# Interfaces.net
KiCad netlist of a schematic drawn in Altium Designer
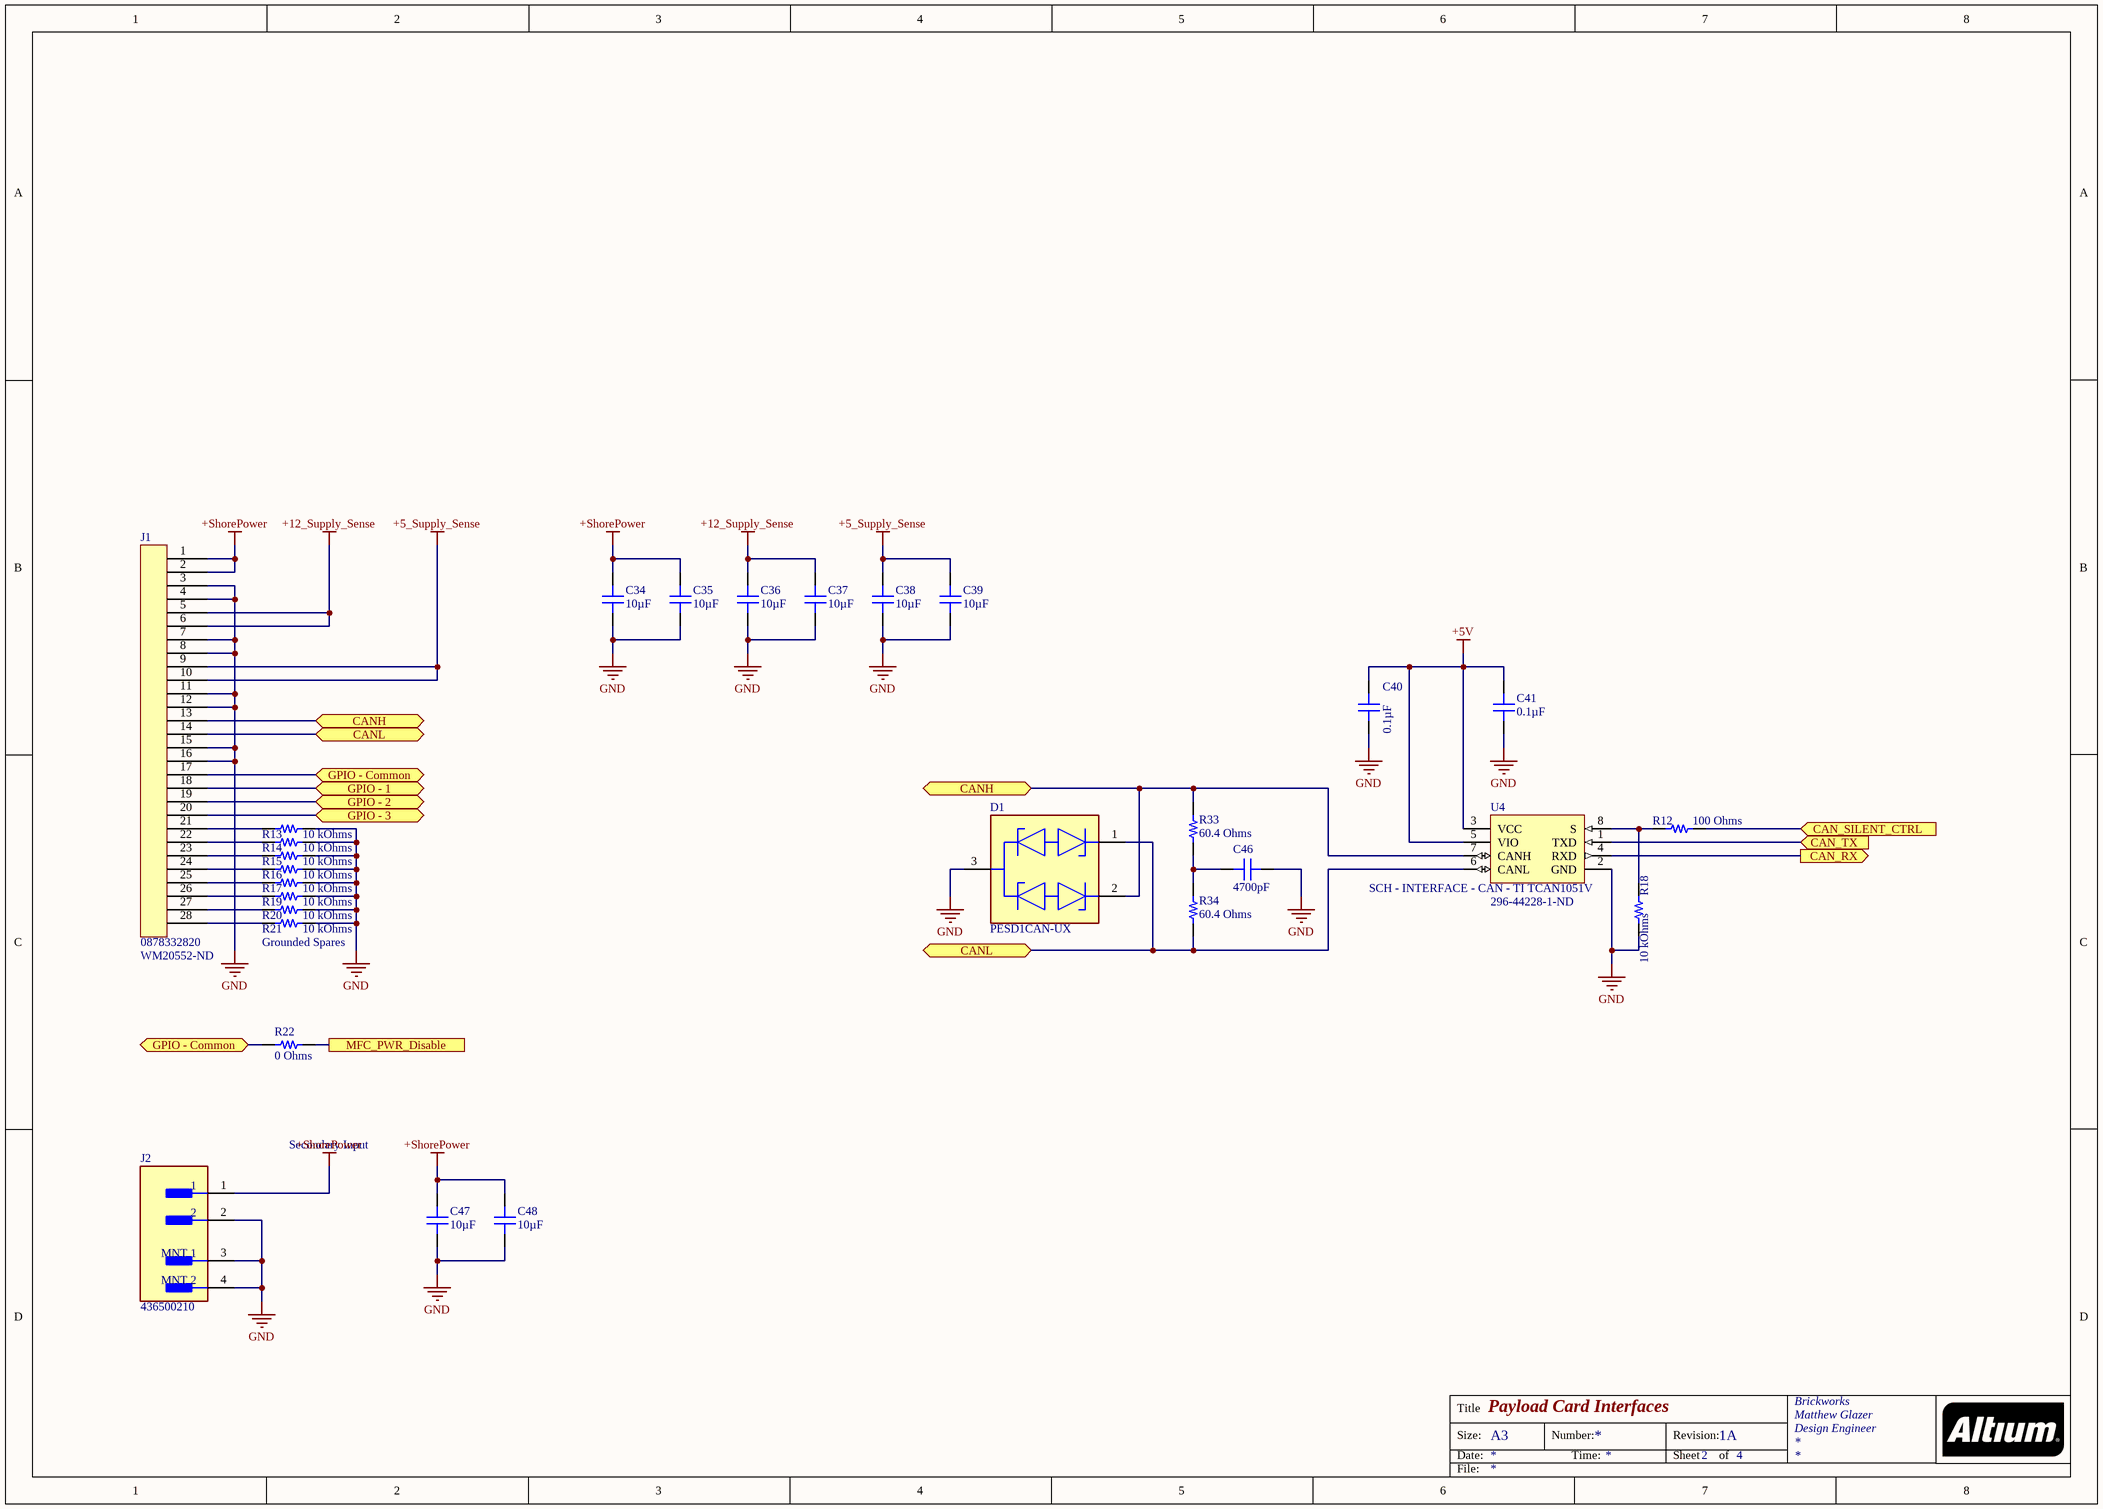
[diagram p0: Interfaces.SchDoc]

(export (version "E")
  (design (tool "Eeschema 10.0.6"))
  (components
    (comp (ref "C34")
      (value "10µF")
      (footprint "CAP 0805_2012")
      (description "CAP CER 10UF 16V X5R 0805")
      (fields (field (name "PART NUMBER") "CC0805KKX5R7BB106") (field (name "MANUFACTURER") "Yageo"))
      (libsource (lib "Celestial Altium Library - altium_library") (part "Capacitor"))
    )
    (comp (ref "C35")
      (value "10µF")
      (footprint "CAP 0805_2012")
      (description "CAP CER 10UF 16V X5R 0805")
      (fields (field (name "PART NUMBER") "CC0805KKX5R7BB106") (field (name "MANUFACTURER") "Yageo"))
      (libsource (lib "Celestial Altium Library - altium_library") (part "Capacitor"))
    )
    (comp (ref "C36")
      (value "10µF")
      (footprint "CAP 0805_2012")
      (description "CAP CER 10UF 16V X5R 0805")
      (fields (field (name "PART NUMBER") "CC0805KKX5R7BB106") (field (name "MANUFACTURER") "Yageo"))
      (libsource (lib "Celestial Altium Library - altium_library") (part "Capacitor"))
    )
    (comp (ref "C37")
      (value "10µF")
      (footprint "CAP 0805_2012")
      (description "CAP CER 10UF 16V X5R 0805")
      (fields (field (name "PART NUMBER") "CC0805KKX5R7BB106") (field (name "MANUFACTURER") "Yageo"))
      (libsource (lib "Celestial Altium Library - altium_library") (part "Capacitor"))
    )
    (comp (ref "C38")
      (value "10µF")
      (footprint "CAP 0805_2012")
      (description "CAP CER 10UF 16V X5R 0805")
      (fields (field (name "PART NUMBER") "CC0805KKX5R7BB106") (field (name "MANUFACTURER") "Yageo"))
      (libsource (lib "Celestial Altium Library - altium_library") (part "Capacitor"))
    )
    (comp (ref "C39")
      (value "10µF")
      (footprint "CAP 0805_2012")
      (description "CAP CER 10UF 16V X5R 0805")
      (fields (field (name "PART NUMBER") "CC0805KKX5R7BB106") (field (name "MANUFACTURER") "Yageo"))
      (libsource (lib "Celestial Altium Library - altium_library") (part "Capacitor"))
    )
    (comp (ref "C40")
      (value "0.1µF")
      (footprint "CAP 0603_1608")
      (description "CAP CER 0.1UF 25V X7R 0603")
      (fields
        (field (name "PART NUMBER") "CL10B104KA8WPNC")
        (field (name "MANUFACTURER") "Samsung Electro-Mechanics")
      )
      (libsource (lib "Celestial Altium Library - altium_library") (part "Capacitor"))
    )
    (comp (ref "C41")
      (value "0.1µF")
      (footprint "CAP 0603_1608")
      (description "CAP CER 0.1UF 25V X7R 0603")
      (fields
        (field (name "PART NUMBER") "CL10B104KA8WPNC")
        (field (name "MANUFACTURER") "Samsung Electro-Mechanics")
      )
      (libsource (lib "Celestial Altium Library - altium_library") (part "Capacitor"))
    )
    (comp (ref "C46")
      (value "4700pF")
      (footprint "CAP 0603_1608")
      (description "CAP CER 4700PF 50V X7R 0603")
      (fields
        (field (name "PART NUMBER") "VJ0603Y472KXACW1BC")
        (field (name "MANUFACTURER") "Vishay Vitramon")
      )
      (libsource (lib "Celestial Altium Library - altium_library") (part "Capacitor"))
    )
    (comp (ref "C47")
      (value "10µF")
      (footprint "CAP 0805_2012")
      (description "CAP CER 10UF 16V X5R 0805")
      (fields (field (name "PART NUMBER") "CC0805KKX5R7BB106") (field (name "MANUFACTURER") "Yageo"))
      (libsource (lib "Celestial Altium Library - altium_library") (part "Capacitor"))
    )
    (comp (ref "C48")
      (value "10µF")
      (footprint "CAP 0805_2012")
      (description "CAP CER 10UF 16V X5R 0805")
      (fields (field (name "PART NUMBER") "CC0805KKX5R7BB106") (field (name "MANUFACTURER") "Yageo"))
      (libsource (lib "Celestial Altium Library - altium_library") (part "Capacitor"))
    )
    (comp (ref "D1")
      (value "PESD1CAN-UX")
      (footprint "FP-SOT323-MFG")
      (description "TVS DIODE 24V 50V SC70-3")
      (libsource (lib "Altium Content Vault") (part "04d57993b6b7b0f5b3c95ba4f97dea0"))
    )
    (comp (ref "J1")
      (value "0878332820")
      (footprint "0878332820")
      (fields (field (name "SUPPLIER PART NUMBER 1") "WM20552-ND"))
      (libsource (lib "HAB_Connectors") (part "0878332820"))
    )
    (comp (ref "J2")
      (value "436500210")
      (footprint "FP-436500210-MFG")
      (description "CONN HEADER SMD R/A 2POS 3MM")
      (fields
        (field (name "MANUFACTURER") "Molex")
        (field (name "OCTOPART") "https://octopart.com/43650-0210-molex-298097")
      )
      (libsource (lib "Altium Content Vault") (part "029478cb6d4f2fad0cd2a245525ee6d"))
    )
    (comp (ref "R12")
      (value "100 Ohms")
      (footprint "RES 0603_1608")
      (description "RES 100 OHM 1% 1/10W 0603")
      (fields
        (field (name "PART NUMBER") "RMCF0603FG100R")
        (field (name "MANUFACTURER") "Stackpole Electronics Inc")
      )
      (libsource (lib "Celestial Altium Library - altium_library") (part "Resistor"))
    )
    (comp (ref "R13")
      (value "10 kOhms")
      (footprint "RES 0603_1608")
      (description "RES 10K OHM 5% 1/10W 0603")
      (fields
        (field (name "PART NUMBER") "RMCF0603JT10K0")
        (field (name "MANUFACTURER") "Stackpole Electronics Inc")
      )
      (libsource (lib "Celestial Altium Library - altium_library") (part "Resistor"))
    )
    (comp (ref "R14")
      (value "10 kOhms")
      (footprint "RES 0603_1608")
      (description "RES 10K OHM 5% 1/10W 0603")
      (fields
        (field (name "PART NUMBER") "RMCF0603JT10K0")
        (field (name "MANUFACTURER") "Stackpole Electronics Inc")
      )
      (libsource (lib "Celestial Altium Library - altium_library") (part "Resistor"))
    )
    (comp (ref "R15")
      (value "10 kOhms")
      (footprint "RES 0603_1608")
      (description "RES 10K OHM 5% 1/10W 0603")
      (fields
        (field (name "PART NUMBER") "RMCF0603JT10K0")
        (field (name "MANUFACTURER") "Stackpole Electronics Inc")
      )
      (libsource (lib "Celestial Altium Library - altium_library") (part "Resistor"))
    )
    (comp (ref "R16")
      (value "10 kOhms")
      (footprint "RES 0603_1608")
      (description "RES 10K OHM 5% 1/10W 0603")
      (fields
        (field (name "PART NUMBER") "RMCF0603JT10K0")
        (field (name "MANUFACTURER") "Stackpole Electronics Inc")
      )
      (libsource (lib "Celestial Altium Library - altium_library") (part "Resistor"))
    )
    (comp (ref "R17")
      (value "10 kOhms")
      (footprint "RES 0603_1608")
      (description "RES 10K OHM 5% 1/10W 0603")
      (fields
        (field (name "PART NUMBER") "RMCF0603JT10K0")
        (field (name "MANUFACTURER") "Stackpole Electronics Inc")
      )
      (libsource (lib "Celestial Altium Library - altium_library") (part "Resistor"))
    )
    (comp (ref "R18")
      (value "10 kOhms")
      (footprint "RES 0603_1608")
      (description "RES 10K OHM 5% 1/10W 0603")
      (fields
        (field (name "PART NUMBER") "RMCF0603JT10K0")
        (field (name "MANUFACTURER") "Stackpole Electronics Inc")
      )
      (libsource (lib "Celestial Altium Library - altium_library") (part "Resistor"))
    )
    (comp (ref "R19")
      (value "10 kOhms")
      (footprint "RES 0603_1608")
      (description "RES 10K OHM 5% 1/10W 0603")
      (fields
        (field (name "PART NUMBER") "RMCF0603JT10K0")
        (field (name "MANUFACTURER") "Stackpole Electronics Inc")
      )
      (libsource (lib "Celestial Altium Library - altium_library") (part "Resistor"))
    )
    (comp (ref "R20")
      (value "10 kOhms")
      (footprint "RES 0603_1608")
      (description "RES 10K OHM 5% 1/10W 0603")
      (fields
        (field (name "PART NUMBER") "RMCF0603JT10K0")
        (field (name "MANUFACTURER") "Stackpole Electronics Inc")
      )
      (libsource (lib "Celestial Altium Library - altium_library") (part "Resistor"))
    )
    (comp (ref "R21")
      (value "10 kOhms")
      (footprint "RES 0603_1608")
      (description "RES 10K OHM 5% 1/10W 0603")
      (fields
        (field (name "PART NUMBER") "RMCF0603JT10K0")
        (field (name "MANUFACTURER") "Stackpole Electronics Inc")
      )
      (libsource (lib "Celestial Altium Library - altium_library") (part "Resistor"))
    )
    (comp (ref "R22")
      (value "0 Ohms")
      (footprint "RES 0603_1608")
      (description "RES 0 OHM JUMPER 1/10W 0603")
      (fields
        (field (name "PART NUMBER") "RMCF0603ZT0R00")
        (field (name "MANUFACTURER") "Stackpole Electronics Inc")
      )
      (libsource (lib "Celestial Altium Library - altium_library") (part "Resistor"))
    )
    (comp (ref "R33")
      (value "60.4 Ohms")
      (footprint "RES 1206_3216")
      (description "RES SMD 60.4 OHM 1% 1/2W 1206")
      (fields (field (name "PART NUMBER") "ESR18EZPF60R4") (field (name "MANUFACTURER") "Rohm Semiconductor"))
      (libsource (lib "Celestial Altium Library - altium_library") (part "Resistor"))
    )
    (comp (ref "R34")
      (value "60.4 Ohms")
      (footprint "RES 1206_3216")
      (description "RES SMD 60.4 OHM 1% 1/2W 1206")
      (fields (field (name "PART NUMBER") "ESR18EZPF60R4") (field (name "MANUFACTURER") "Rohm Semiconductor"))
      (libsource (lib "Celestial Altium Library - altium_library") (part "Resistor"))
    )
    (comp (ref "U4")
      (value "SCH - INTERFACE - CAN - TI TCAN1051V")
      (footprint "PCB - LEADS - SOIC - TI SOIC-8")
      (fields (field (name "SUPPLIER PART NUMBER 1") "296-44228-1-ND"))
      (libsource (lib "HAB_ICs") (part "SCH - INTERFACE - CAN - TI TCAN1051V"))
    )
  )
  (nets
    (net (code "1") (name "+5V") (class "Default")
      (node (ref "C40") (pin "2") (pinfunction "2_2") (pintype "passive"))
      (node (ref "C41") (pin "2") (pinfunction "2_2") (pintype "passive"))
      (node (ref "U4") (pin "3") (pinfunction "VCC_3") (pintype "power_in"))
      (node (ref "U4") (pin "5") (pinfunction "VIO_5") (pintype "power_in"))
    )
    (net (code "2") (name "+5_Supply_Sense") (class "Default")
      (node (ref "C38") (pin "2") (pinfunction "2_2") (pintype "passive"))
      (node (ref "C39") (pin "2") (pinfunction "2_2") (pintype "passive"))
      (node (ref "J1") (pin "10") (pintype "passive"))
      (node (ref "J1") (pin "9") (pintype "passive"))
    )
    (net (code "3") (name "+12_Supply_Sense") (class "Default")
      (node (ref "C36") (pin "2") (pinfunction "2_2") (pintype "passive"))
      (node (ref "C37") (pin "2") (pinfunction "2_2") (pintype "passive"))
      (node (ref "J1") (pin "5") (pintype "passive"))
      (node (ref "J1") (pin "6") (pintype "passive"))
    )
    (net (code "4") (name "+ShorePower") (class "Default")
      (node (ref "C34") (pin "2") (pinfunction "2_2") (pintype "passive"))
      (node (ref "C35") (pin "2") (pinfunction "2_2") (pintype "passive"))
      (node (ref "C47") (pin "2") (pinfunction "2_2") (pintype "passive"))
      (node (ref "C48") (pin "2") (pinfunction "2_2") (pintype "passive"))
      (node (ref "J1") (pin "1") (pintype "passive"))
      (node (ref "J1") (pin "2") (pintype "passive"))
      (node (ref "J2") (pin "1") (pinfunction "1_1") (pintype "passive"))
    )
    (net (code "5") (name "/CANH") (class "Default")
      (node (ref "D1") (pin "2") (pinfunction "cathode_2_2") (pintype "passive"))
      (node (ref "J1") (pin "13") (pintype "passive"))
      (node (ref "R33") (pin "2") (pinfunction "2_2") (pintype "passive"))
      (node (ref "U4") (pin "7") (pinfunction "CANH_7") (pintype "bidirectional"))
    )
    (net (code "6") (name "/CANL") (class "Default")
      (node (ref "D1") (pin "1") (pinfunction "cathode_1_1") (pintype "passive"))
      (node (ref "J1") (pin "14") (pintype "passive"))
      (node (ref "R34") (pin "1") (pinfunction "1_1") (pintype "passive"))
      (node (ref "U4") (pin "6") (pinfunction "CANL_6") (pintype "bidirectional"))
    )
    (net (code "7") (name "/CAN_RX") (class "Default")
      (node (ref "U4") (pin "4") (pinfunction "RXD_4") (pintype "output"))
    )
    (net (code "8") (name "/CAN_SILENT_CTRL") (class "Default")
      (node (ref "R12") (pin "2") (pinfunction "2_2") (pintype "passive"))
    )
    (net (code "9") (name "/CAN_TX") (class "Default")
      (node (ref "U4") (pin "1") (pinfunction "TXD_1") (pintype "input"))
    )
    (net (code "10") (name "/GPIO - 1") (class "Default") (node (ref "J1") (pin "18") (pintype "passive")))
    (net (code "11") (name "/GPIO - 2") (class "Default") (node (ref "J1") (pin "19") (pintype "passive")))
    (net (code "12") (name "/GPIO - 3") (class "Default") (node (ref "J1") (pin "20") (pintype "passive")))
    (net (code "13") (name "/GPIO - Common") (class "Default")
      (node (ref "J1") (pin "17") (pintype "passive"))
      (node (ref "R22") (pin "1") (pinfunction "1_1") (pintype "passive"))
    )
    (net (code "14") (name "/MFC_PWR_Disable") (class "Default")
      (node (ref "R22") (pin "2") (pinfunction "2_2") (pintype "passive"))
    )
    (net (code "15") (name "GND") (class "Default")
      (node (ref "C34") (pin "1") (pinfunction "1_1") (pintype "passive"))
      (node (ref "C35") (pin "1") (pinfunction "1_1") (pintype "passive"))
      (node (ref "C36") (pin "1") (pinfunction "1_1") (pintype "passive"))
      (node (ref "C37") (pin "1") (pinfunction "1_1") (pintype "passive"))
      (node (ref "C38") (pin "1") (pinfunction "1_1") (pintype "passive"))
      (node (ref "C39") (pin "1") (pinfunction "1_1") (pintype "passive"))
      (node (ref "C40") (pin "1") (pinfunction "1_1") (pintype "passive"))
      (node (ref "C41") (pin "1") (pinfunction "1_1") (pintype "passive"))
      (node (ref "C46") (pin "2") (pinfunction "2_2") (pintype "passive"))
      (node (ref "C47") (pin "1") (pinfunction "1_1") (pintype "passive"))
      (node (ref "C48") (pin "1") (pinfunction "1_1") (pintype "passive"))
      (node (ref "D1") (pin "3") (pinfunction "common_cathode_3") (pintype "passive"))
      (node (ref "J1") (pin "11") (pintype "passive"))
      (node (ref "J1") (pin "12") (pintype "passive"))
      (node (ref "J1") (pin "15") (pintype "passive"))
      (node (ref "J1") (pin "16") (pintype "passive"))
      (node (ref "J1") (pin "3") (pintype "passive"))
      (node (ref "J1") (pin "4") (pintype "passive"))
      (node (ref "J1") (pin "7") (pintype "passive"))
      (node (ref "J1") (pin "8") (pintype "passive"))
      (node (ref "J2") (pin "2") (pinfunction "2_2") (pintype "passive"))
      (node (ref "J2") (pin "3") (pinfunction "MNT_1_3") (pintype "passive"))
      (node (ref "J2") (pin "4") (pinfunction "MNT_2_4") (pintype "passive"))
      (node (ref "R13") (pin "2") (pinfunction "2_2") (pintype "passive"))
      (node (ref "R14") (pin "2") (pinfunction "2_2") (pintype "passive"))
      (node (ref "R15") (pin "2") (pinfunction "2_2") (pintype "passive"))
      (node (ref "R16") (pin "2") (pinfunction "2_2") (pintype "passive"))
      (node (ref "R17") (pin "2") (pinfunction "2_2") (pintype "passive"))
      (node (ref "R18") (pin "1") (pinfunction "1_1") (pintype "passive"))
      (node (ref "R19") (pin "2") (pinfunction "2_2") (pintype "passive"))
      (node (ref "R20") (pin "2") (pinfunction "2_2") (pintype "passive"))
      (node (ref "R21") (pin "2") (pinfunction "2_2") (pintype "passive"))
      (node (ref "U4") (pin "2") (pinfunction "GND_2") (pintype "power_in"))
    )
    (net (code "16") (name "Net-(C46-Pad1)") (class "Default")
      (node (ref "C46") (pin "1") (pinfunction "1_1") (pintype "passive"))
      (node (ref "R33") (pin "1") (pinfunction "1_1") (pintype "passive"))
      (node (ref "R34") (pin "2") (pinfunction "2_2") (pintype "passive"))
    )
    (net (code "17") (name "Net-(J1-Pad21)") (class "Default")
      (node (ref "J1") (pin "21") (pintype "passive"))
      (node (ref "R13") (pin "1") (pinfunction "1_1") (pintype "passive"))
    )
    (net (code "18") (name "Net-(J1-Pad22)") (class "Default")
      (node (ref "J1") (pin "22") (pintype "passive"))
      (node (ref "R14") (pin "1") (pinfunction "1_1") (pintype "passive"))
    )
    (net (code "19") (name "Net-(J1-Pad23)") (class "Default")
      (node (ref "J1") (pin "23") (pintype "passive"))
      (node (ref "R15") (pin "1") (pinfunction "1_1") (pintype "passive"))
    )
    (net (code "20") (name "Net-(J1-Pad24)") (class "Default")
      (node (ref "J1") (pin "24") (pintype "passive"))
      (node (ref "R16") (pin "1") (pinfunction "1_1") (pintype "passive"))
    )
    (net (code "21") (name "Net-(J1-Pad25)") (class "Default")
      (node (ref "J1") (pin "25") (pintype "passive"))
      (node (ref "R17") (pin "1") (pinfunction "1_1") (pintype "passive"))
    )
    (net (code "22") (name "Net-(J1-Pad26)") (class "Default")
      (node (ref "J1") (pin "26") (pintype "passive"))
      (node (ref "R19") (pin "1") (pinfunction "1_1") (pintype "passive"))
    )
    (net (code "23") (name "Net-(J1-Pad27)") (class "Default")
      (node (ref "J1") (pin "27") (pintype "passive"))
      (node (ref "R20") (pin "1") (pinfunction "1_1") (pintype "passive"))
    )
    (net (code "24") (name "Net-(J1-Pad28)") (class "Default")
      (node (ref "J1") (pin "28") (pintype "passive"))
      (node (ref "R21") (pin "1") (pinfunction "1_1") (pintype "passive"))
    )
    (net (code "25") (name "Net-(U4-S)") (class "Default")
      (node (ref "R12") (pin "1") (pinfunction "1_1") (pintype "passive"))
      (node (ref "R18") (pin "2") (pinfunction "2_2") (pintype "passive"))
      (node (ref "U4") (pin "8") (pinfunction "S_8") (pintype "input"))
    )
  )
)
